# Temp_Sensor.net
KiCad netlist of a schematic drawn in Altium Designer
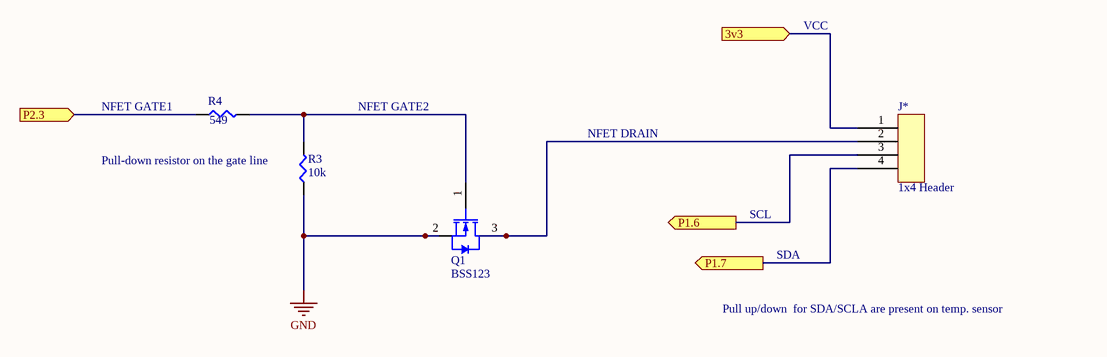
[diagram p0: Temp_Sensor.SchDoc]

(export (version "E")
  (design (tool "Eeschema 10.0.6"))
  (components
    (comp (ref "J*")
      (value "1x4 Header")
      (footprint "1X4 HEADER")
      (description "CONN HEADER VERT 4POS 2.54MM")
      (fields
        (field (name "MANUFACTURER") "Würth Elektronik")
        (field (name "MANUFACTURER PART NUMBER") "61300411121")
      )
      (libsource (lib "URC_Lib") (part "1X4 HEADER"))
    )
    (comp (ref "Q1")
      (value "BSS123")
      (footprint "FAIR-SOT23-3_V")
      (fields (field (name "MANUFACTURER") "Fairchild"))
      (libsource (lib "Altium Content Vault") (part "NEMOS-GSD-3"))
    )
    (comp (ref "R3")
      (value "10k")
      (footprint "SMD-0805-RES")
      (description "RES SMD 10K OHM 1% 1/2W 0805")
      (fields
        (field (name "PART NUMBER") "ERJ-P06F1002V")
        (field (name "DIGI-KEY PART NUMBER") "P16059CT-ND")
      )
      (libsource (lib "Panasonic_resistor_0805") (part "ERJ-P06F1002V"))
    )
    (comp (ref "R4")
      (value "549")
      (footprint "SMD-0805-RES")
      (description "RES SMD 549 OHM 1% 1/8W 0805")
      (fields (field (name "PART NUMBER") "ERJ-6ENF5490V") (field (name "DIGI-KEY PART NUMBER") "P549CCT-ND"))
      (libsource (lib "Panasonic_resistor_0805") (part "ERJ-6ENF5490V"))
    )
  )
  (nets
    (net (code "1") (name "/3v3") (class "Default")
      (node (ref "J*") (pin "1") (pinfunction "1_1") (pintype "passive"))
    )
    (net (code "2") (name "/P1.6") (class "Default")
      (node (ref "J*") (pin "3") (pinfunction "3_3") (pintype "passive"))
    )
    (net (code "3") (name "/P1.7") (class "Default")
      (node (ref "J*") (pin "4") (pinfunction "4_4") (pintype "passive"))
    )
    (net (code "4") (name "/P2.3") (class "Default")
      (node (ref "R4") (pin "1") (pinfunction "1_1") (pintype "passive"))
    )
    (net (code "5") (name "GND") (class "Default")
      (node (ref "Q1") (pin "2") (pinfunction "S_2") (pintype "passive"))
      (node (ref "R3") (pin "1") (pinfunction "1_1") (pintype "passive"))
    )
    (net (code "6") (name "Net-(Q1-D)") (class "Default")
      (node (ref "J*") (pin "2") (pinfunction "2_2") (pintype "passive"))
      (node (ref "Q1") (pin "3") (pinfunction "D_3") (pintype "passive"))
    )
    (net (code "7") (name "Net-(Q1-G)") (class "Default")
      (node (ref "Q1") (pin "1") (pinfunction "G_1") (pintype "passive"))
      (node (ref "R3") (pin "2") (pinfunction "2_2") (pintype "passive"))
      (node (ref "R4") (pin "2") (pinfunction "2_2") (pintype "passive"))
    )
  )
)
